# Reader.net
KiCad netlist of a schematic drawn in EAGLE
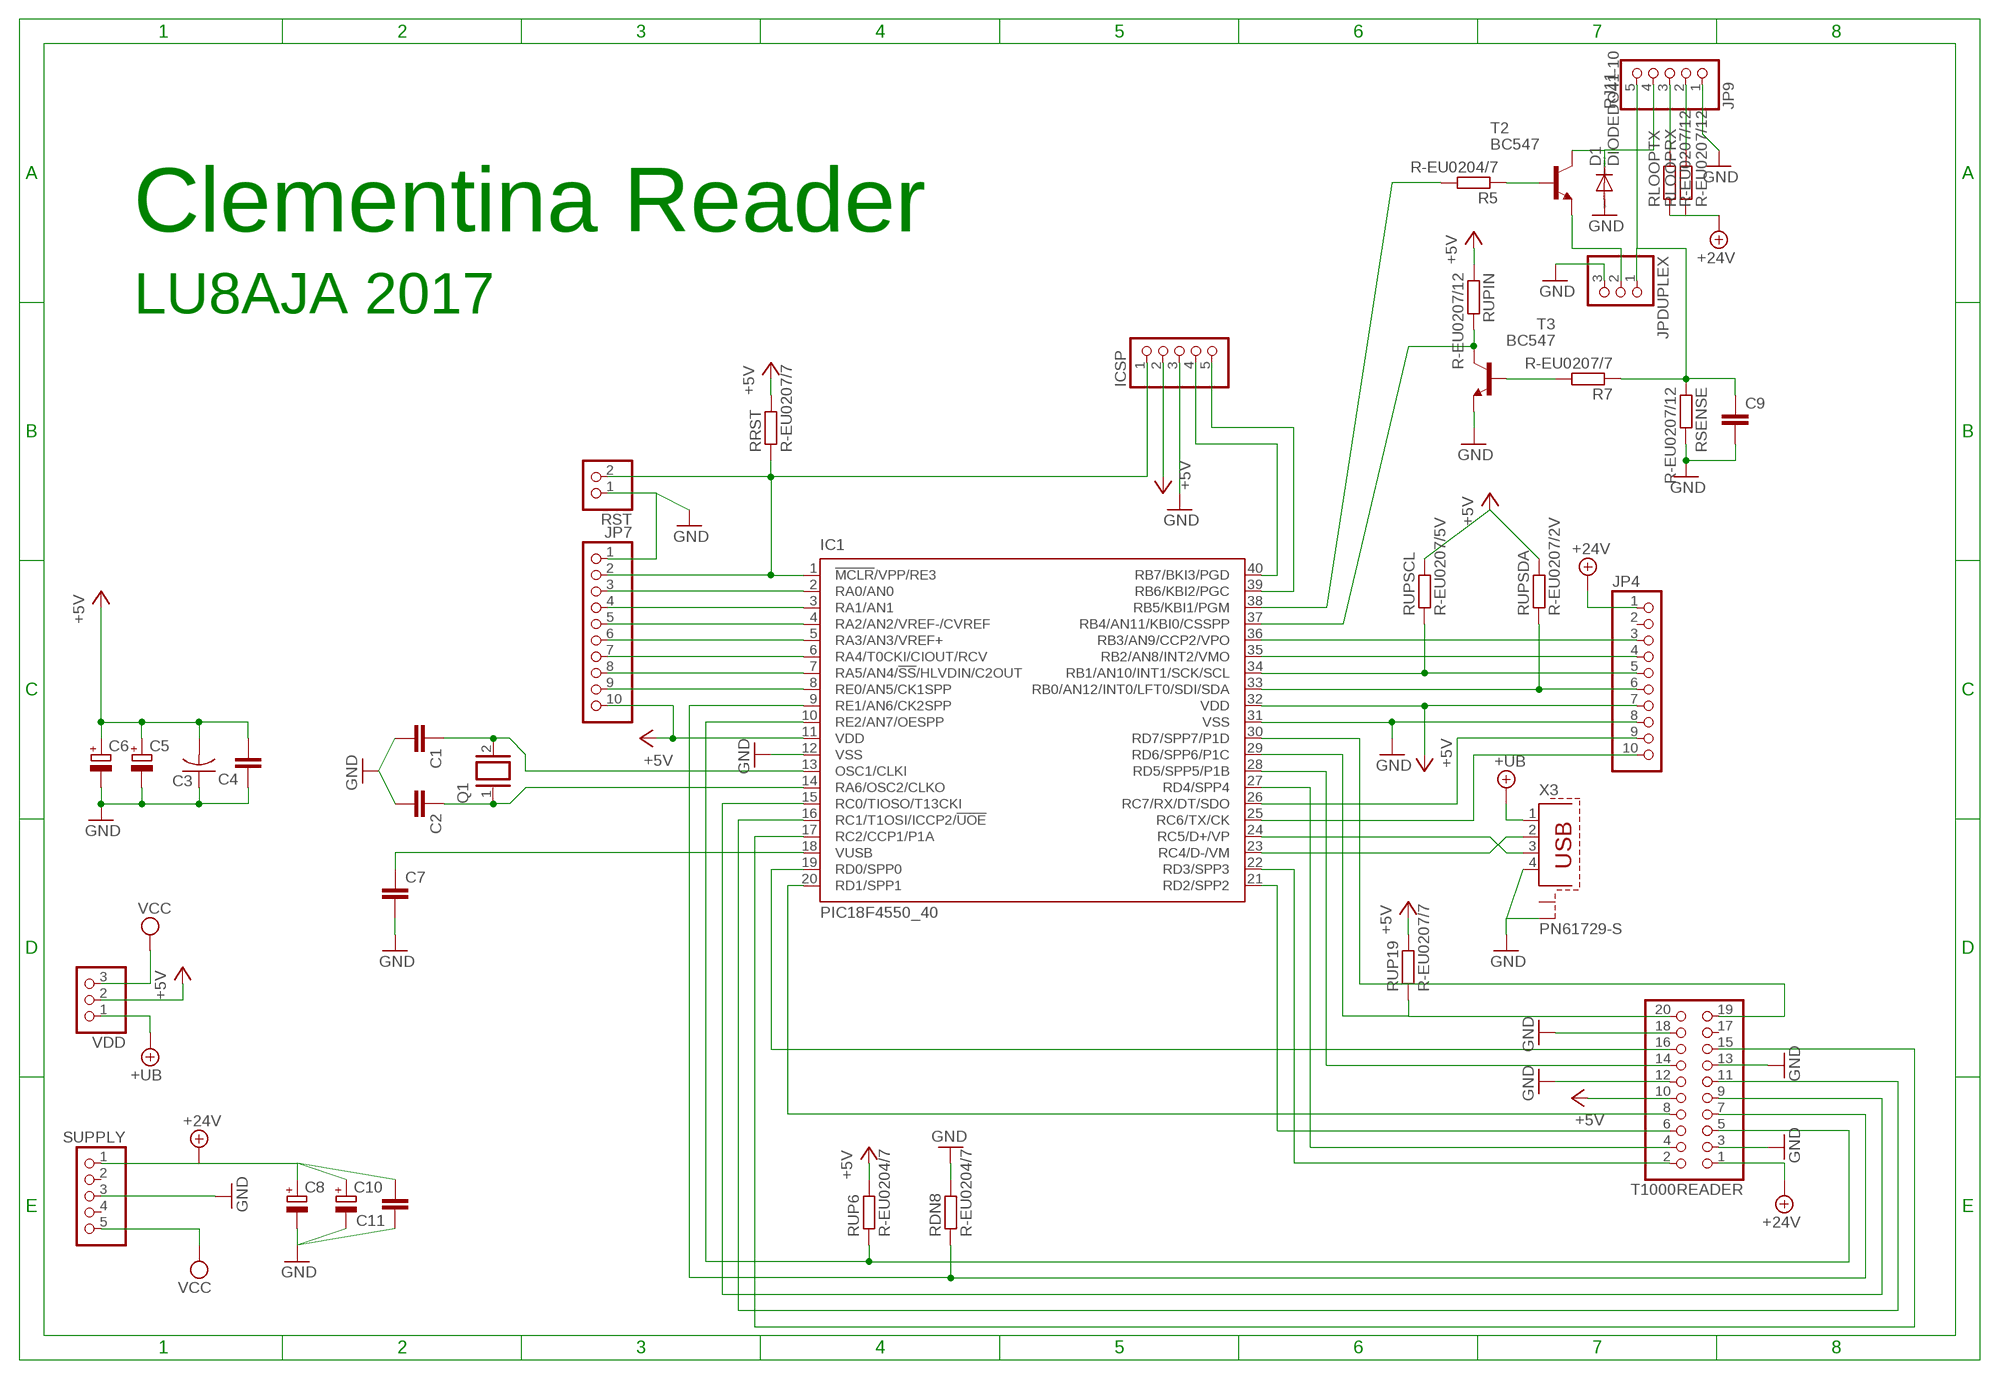
[diagram p0: schematic, sheet 1]

(export (version "E")
  (design (tool "Eeschema 10.0.6"))
  (components
    (comp (ref "C1")
      (value "C-EU025-025X050")
      (footprint "eagle-import:C025-025X050")
      (libsource (lib "eagle-import") (part "rcl_C-EU025-025X050"))
    )
    (comp (ref "C2")
      (value "C-EU025-025X050")
      (footprint "eagle-import:C025-025X050")
      (libsource (lib "eagle-import") (part "rcl_C-EU025-025X050"))
    )
    (comp (ref "C3")
      (value "C-US025-024X044")
      (footprint "eagle-import:C025-024X044")
      (libsource (lib "eagle-import") (part "C-US025-024X044"))
    )
    (comp (ref "C4")
      (value "C-EU025-030X050")
      (footprint "eagle-import:C025-030X050")
      (libsource (lib "eagle-import") (part "C-EU025-030X050"))
    )
    (comp (ref "C5")
      (value "CPOL-EUE2.5-6")
      (footprint "eagle-import:E2,5-6")
      (libsource (lib "eagle-import") (part "CPOL-EUE2.5-6"))
    )
    (comp (ref "C6")
      (value "CPOL-EUE5-8.5")
      (footprint "eagle-import:E5-8,5")
      (libsource (lib "eagle-import") (part "rcl_CPOL-EUE5-8.5"))
    )
    (comp (ref "C7")
      (value "C-EU050-025X075")
      (footprint "eagle-import:C050-025X075")
      (libsource (lib "eagle-import") (part "C-EU050-025X075"))
    )
    (comp (ref "C8")
      (value "CPOL-EUE5-8.5")
      (footprint "eagle-import:E5-8,5")
      (libsource (lib "eagle-import") (part "CPOL-EUE5-8.5"))
    )
    (comp (ref "C9")
      (value "C-EU050-024X044")
      (footprint "eagle-import:C050-024X044")
      (libsource (lib "eagle-import") (part "C-EU050-024X044"))
    )
    (comp (ref "C10")
      (value "CPOL-EUE5-8.5")
      (footprint "eagle-import:E5-8,5")
      (libsource (lib "eagle-import") (part "CPOL-EUE5-8.5"))
    )
    (comp (ref "C11")
      (value "C-EU025-030X050")
      (footprint "eagle-import:C025-030X050")
      (libsource (lib "eagle-import") (part "C-EU025-030X050"))
    )
    (comp (ref "D1")
      (value "DIODEDO41-10")
      (footprint "eagle-import:DO41-10")
      (libsource (lib "eagle-import") (part "DIODEDO41-10"))
    )
    (comp (ref "IC1")
      (value "PIC18F4550_40")
      (footprint "eagle-import:DIL40")
      (fields (field (name "MF") "MICROCHIP") (field (name "MPN") "PIC18F4550-I/P"))
      (libsource (lib "eagle-import") (part "PIC18F4_40550"))
    )
    (comp (ref "ICSP")
      (value "PINHD-1X5")
      (footprint "eagle-import:1X05")
      (libsource (lib "eagle-import") (part "PINHD-1X5"))
    )
    (comp (ref "JP4")
      (value "PINHD-1X10")
      (footprint "eagle-import:1X10")
      (libsource (lib "eagle-import") (part "PINHD-1X10"))
    )
    (comp (ref "JP7")
      (value "PINHD-1X10")
      (footprint "eagle-import:1X10")
      (libsource (lib "eagle-import") (part "PINHD-1X10"))
    )
    (comp (ref "JP9")
      (value "RJ11")
      (footprint "eagle-import:1X05")
      (libsource (lib "eagle-import") (part "PINHD-1X5"))
    )
    (comp (ref "JPDUPLEX")
      (value "PINHD-1X3")
      (footprint "eagle-import:1X03")
      (libsource (lib "eagle-import") (part "PINHD-1X3"))
    )
    (comp (ref "Q1")
      (value "XTAL/S")
      (footprint "eagle-import:QS")
      (libsource (lib "eagle-import") (part "XTAL/S"))
    )
    (comp (ref "R5")
      (value "R-EU0204/7")
      (footprint "eagle-import:0204_7")
      (libsource (lib "eagle-import") (part "R-EU0204/7"))
    )
    (comp (ref "R7")
      (value "R-EU0207/7")
      (footprint "eagle-import:0207_7")
      (libsource (lib "eagle-import") (part "R-EU0207/7"))
    )
    (comp (ref "RDN8")
      (value "R-EU0204/7")
      (footprint "eagle-import:0204_7")
      (libsource (lib "eagle-import") (part "R-EU0204/7"))
    )
    (comp (ref "RLOOPRX")
      (value "R-EU0207/12")
      (footprint "eagle-import:0207_12")
      (libsource (lib "eagle-import") (part "R-EU0207/12"))
    )
    (comp (ref "RLOOPTX")
      (value "R-EU0207/12")
      (footprint "eagle-import:0207_12")
      (libsource (lib "eagle-import") (part "R-EU0207/12"))
    )
    (comp (ref "RRST")
      (value "R-EU0207/7")
      (footprint "eagle-import:0207_7")
      (libsource (lib "eagle-import") (part "R-EU0207/7"))
    )
    (comp (ref "RSENSE")
      (value "R-EU0207/12")
      (footprint "eagle-import:0207_12")
      (libsource (lib "eagle-import") (part "R-EU0207/12"))
    )
    (comp (ref "RST")
      (value "PINHD-1X2")
      (footprint "eagle-import:1X02")
      (libsource (lib "eagle-import") (part "PINHD-1X2"))
    )
    (comp (ref "RUP6")
      (value "R-EU0204/7")
      (footprint "eagle-import:0204_7")
      (libsource (lib "eagle-import") (part "R-EU0204/7"))
    )
    (comp (ref "RUP19")
      (value "R-EU0207/7")
      (footprint "eagle-import:0207_7")
      (libsource (lib "eagle-import") (part "R-EU0207/7"))
    )
    (comp (ref "RUPIN")
      (value "R-EU0207/12")
      (footprint "eagle-import:0207_12")
      (libsource (lib "eagle-import") (part "R-EU0207/12"))
    )
    (comp (ref "RUPSCL")
      (value "R-EU0207/5V")
      (footprint "eagle-import:0207_5V")
      (libsource (lib "eagle-import") (part "R-EU0207/5V"))
    )
    (comp (ref "RUPSDA")
      (value "R-EU0207/2V")
      (footprint "eagle-import:0207_2V")
      (libsource (lib "eagle-import") (part "R-EU0207/2V"))
    )
    (comp (ref "SUPPLY")
      (value "PINHD-1X5")
      (footprint "eagle-import:1X05")
      (libsource (lib "eagle-import") (part "PINHD-1X5"))
    )
    (comp (ref "T2")
      (value "BC547")
      (footprint "eagle-import:TO92")
      (libsource (lib "eagle-import") (part "BC547"))
    )
    (comp (ref "T3")
      (value "BC547")
      (footprint "eagle-import:TO92")
      (libsource (lib "eagle-import") (part "BC547"))
    )
    (comp (ref "T1000READER")
      (value "PINHD-2X10")
      (footprint "eagle-import:2X10")
      (libsource (lib "eagle-import") (part "PINHD-2X10"))
    )
    (comp (ref "VDD")
      (value "PINHD-1X3")
      (footprint "eagle-import:1X03")
      (libsource (lib "eagle-import") (part "PINHD-1X3"))
    )
    (comp (ref "X3")
      (value "PN61729-S")
      (footprint "eagle-import:PN61729-S")
      (libsource (lib "eagle-import") (part "PN61729-S"))
    )
  )
  (nets
    (net (code "1") (name "+5V") (class "Default")
      (node (ref "C3") (pin "2") (pinfunction "2_2") (pintype "passive"))
      (node (ref "C4") (pin "2") (pinfunction "2_2") (pintype "passive"))
      (node (ref "C5") (pin "+") (pinfunction "+_+") (pintype "passive"))
      (node (ref "C6") (pin "+") (pinfunction "+_+") (pintype "passive"))
      (node (ref "IC1") (pin "11") (pinfunction "VDD_11") (pintype "power_in"))
      (node (ref "IC1") (pin "32") (pinfunction "VDD_32") (pintype "power_in"))
      (node (ref "ICSP") (pin "2") (pinfunction "2_2") (pintype "passive"))
      (node (ref "JP4") (pin "7") (pinfunction "7_7") (pintype "passive"))
      (node (ref "JP7") (pin "10") (pinfunction "10_10") (pintype "passive"))
      (node (ref "RRST") (pin "2") (pinfunction "2_2") (pintype "passive"))
      (node (ref "RUP19") (pin "2") (pinfunction "2_2") (pintype "passive"))
      (node (ref "RUP6") (pin "2") (pinfunction "2_2") (pintype "passive"))
      (node (ref "RUPIN") (pin "1") (pinfunction "1_1") (pintype "passive"))
      (node (ref "RUPSCL") (pin "2") (pinfunction "2_2") (pintype "passive"))
      (node (ref "RUPSDA") (pin "2") (pinfunction "2_2") (pintype "passive"))
      (node (ref "T1000READER") (pin "10") (pinfunction "10_10") (pintype "passive"))
      (node (ref "VDD") (pin "2") (pinfunction "2_2") (pintype "passive"))
    )
    (net (code "2") (name "+24V") (class "Default")
      (node (ref "C10") (pin "+") (pinfunction "+_+") (pintype "passive"))
      (node (ref "C11") (pin "2") (pinfunction "2_2") (pintype "passive"))
      (node (ref "C8") (pin "+") (pinfunction "+_+") (pintype "passive"))
      (node (ref "JP4") (pin "1") (pinfunction "1_1") (pintype "passive"))
      (node (ref "RLOOPRX") (pin "1") (pinfunction "1_1") (pintype "passive"))
      (node (ref "RLOOPTX") (pin "1") (pinfunction "1_1") (pintype "passive"))
      (node (ref "SUPPLY") (pin "1") (pinfunction "1_1") (pintype "passive"))
      (node (ref "T1000READER") (pin "1") (pinfunction "1_1") (pintype "passive"))
    )
    (net (code "3") (name "+UB") (class "Default")
      (node (ref "VDD") (pin "1") (pinfunction "1_1") (pintype "passive"))
      (node (ref "X3") (pin "1") (pinfunction "1_1") (pintype "passive"))
    )
    (net (code "4") (name "GND") (class "Default")
      (node (ref "C1") (pin "2") (pinfunction "2_2") (pintype "passive"))
      (node (ref "C10") (pin "-") (pinfunction "-_-") (pintype "passive"))
      (node (ref "C11") (pin "1") (pinfunction "1_1") (pintype "passive"))
      (node (ref "C2") (pin "2") (pinfunction "2_2") (pintype "passive"))
      (node (ref "C3") (pin "1") (pinfunction "1_1") (pintype "passive"))
      (node (ref "C4") (pin "1") (pinfunction "1_1") (pintype "passive"))
      (node (ref "C5") (pin "-") (pinfunction "-_-") (pintype "passive"))
      (node (ref "C6") (pin "-") (pinfunction "-_-") (pintype "passive"))
      (node (ref "C7") (pin "2") (pinfunction "2_2") (pintype "passive"))
      (node (ref "C8") (pin "-") (pinfunction "-_-") (pintype "passive"))
      (node (ref "C9") (pin "2") (pinfunction "2_2") (pintype "passive"))
      (node (ref "D1") (pin "A") (pinfunction "A_A") (pintype "passive"))
      (node (ref "IC1") (pin "12") (pinfunction "VSS_12") (pintype "power_in"))
      (node (ref "IC1") (pin "31") (pinfunction "VSS_31") (pintype "power_in"))
      (node (ref "ICSP") (pin "3") (pinfunction "3_3") (pintype "passive"))
      (node (ref "JP4") (pin "8") (pinfunction "8_8") (pintype "passive"))
      (node (ref "JP7") (pin "1") (pinfunction "1_1") (pintype "passive"))
      (node (ref "JP9") (pin "1") (pinfunction "1_1") (pintype "passive"))
      (node (ref "JPDUPLEX") (pin "3") (pinfunction "3_3") (pintype "passive"))
      (node (ref "RDN8") (pin "2") (pinfunction "2_2") (pintype "passive"))
      (node (ref "RSENSE") (pin "2") (pinfunction "2_2") (pintype "passive"))
      (node (ref "RST") (pin "1") (pinfunction "1_1") (pintype "passive"))
      (node (ref "SUPPLY") (pin "3") (pinfunction "3_3") (pintype "passive"))
      (node (ref "T1000READER") (pin "12") (pinfunction "12_12") (pintype "passive"))
      (node (ref "T1000READER") (pin "13") (pinfunction "13_13") (pintype "passive"))
      (node (ref "T1000READER") (pin "18") (pinfunction "18_18") (pintype "passive"))
      (node (ref "T1000READER") (pin "3") (pinfunction "3_3") (pintype "passive"))
      (node (ref "T3") (pin "1") (pinfunction "E_1") (pintype "passive"))
      (node (ref "X3") (pin "4") (pinfunction "4_4") (pintype "passive"))
      (node (ref "X3") (pin "S2") (pinfunction "S2_S2") (pintype "passive"))
    )
    (net (code "5") (name "Net-(C9-Pad1)") (class "Default")
      (node (ref "C9") (pin "1") (pinfunction "1_1") (pintype "passive"))
      (node (ref "JP9") (pin "5") (pinfunction "5_5") (pintype "passive"))
      (node (ref "JPDUPLEX") (pin "1") (pinfunction "1_1") (pintype "passive"))
      (node (ref "R7") (pin "1") (pinfunction "1_1") (pintype "passive"))
      (node (ref "RSENSE") (pin "1") (pinfunction "1_1") (pintype "passive"))
    )
    (net (code "6") (name "Net-(IC1-OSC1{slash}CLKI)") (class "Default")
      (node (ref "C1") (pin "1") (pinfunction "1_1") (pintype "passive"))
      (node (ref "IC1") (pin "13") (pinfunction "OSC1/CLKI_13") (pintype "input"))
      (node (ref "Q1") (pin "2") (pinfunction "2_2") (pintype "passive"))
    )
    (net (code "7") (name "Net-(IC1-RA0{slash}AN0)") (class "Default")
      (node (ref "IC1") (pin "2") (pinfunction "RA0/AN0_2") (pintype "bidirectional"))
      (node (ref "JP7") (pin "3") (pinfunction "3_3") (pintype "passive"))
    )
    (net (code "8") (name "Net-(IC1-RA1{slash}AN1)") (class "Default")
      (node (ref "IC1") (pin "3") (pinfunction "RA1/AN1_3") (pintype "bidirectional"))
      (node (ref "JP7") (pin "4") (pinfunction "4_4") (pintype "passive"))
    )
    (net (code "9") (name "Net-(IC1-RA2{slash}AN2{slash}VREF-{slash}CVREF)") (class "Default")
      (node (ref "IC1") (pin "4") (pinfunction "RA2/AN2/VREF-/CVREF_4") (pintype "bidirectional"))
      (node (ref "JP7") (pin "5") (pinfunction "5_5") (pintype "passive"))
    )
    (net (code "10") (name "Net-(IC1-RA3{slash}AN3{slash}VREF+)") (class "Default")
      (node (ref "IC1") (pin "5") (pinfunction "RA3/AN3/VREF+_5") (pintype "bidirectional"))
      (node (ref "JP7") (pin "6") (pinfunction "6_6") (pintype "passive"))
    )
    (net (code "11") (name "Net-(IC1-RA4{slash}T0CKI{slash}CIOUT{slash}RCV)") (class "Default")
      (node (ref "IC1") (pin "6") (pinfunction "RA4/T0CKI/CIOUT/RCV_6") (pintype "bidirectional"))
      (node (ref "JP7") (pin "7") (pinfunction "7_7") (pintype "passive"))
    )
    (net (code "12") (name "Net-(IC1-RA5{slash}AN4{slash}~{SS}{slash}HLVDIN{slash}C2OUT)") (class "Default")
      (node (ref "IC1") (pin "7") (pinfunction "RA5/AN4/~{SS}/HLVDIN/C2OUT_7") (pintype "bidirectional"))
      (node (ref "JP7") (pin "8") (pinfunction "8_8") (pintype "passive"))
    )
    (net (code "13") (name "Net-(IC1-RA6{slash}OSC2{slash}CLKO)") (class "Default")
      (node (ref "C2") (pin "1") (pinfunction "1_1") (pintype "passive"))
      (node (ref "IC1") (pin "14") (pinfunction "RA6/OSC2/CLKO_14") (pintype "output"))
      (node (ref "Q1") (pin "1") (pinfunction "1_1") (pintype "passive"))
    )
    (net (code "14") (name "Net-(IC1-RB0{slash}AN12{slash}INT0{slash}LFT0{slash}SDI{slash}SDA)") (class "Default")
      (node (ref "IC1") (pin "33") (pinfunction "RB0/AN12/INT0/LFT0/SDI/SDA_33") (pintype "bidirectional"))
      (node (ref "JP4") (pin "6") (pinfunction "6_6") (pintype "passive"))
      (node (ref "RUPSDA") (pin "1") (pinfunction "1_1") (pintype "passive"))
    )
    (net (code "15") (name "Net-(IC1-RB1{slash}AN10{slash}INT1{slash}SCK{slash}SCL)") (class "Default")
      (node (ref "IC1") (pin "34") (pinfunction "RB1/AN10/INT1/SCK/SCL_34") (pintype "bidirectional"))
      (node (ref "JP4") (pin "5") (pinfunction "5_5") (pintype "passive"))
      (node (ref "RUPSCL") (pin "1") (pinfunction "1_1") (pintype "passive"))
    )
    (net (code "16") (name "Net-(IC1-RB2{slash}AN8{slash}INT2{slash}VMO)") (class "Default")
      (node (ref "IC1") (pin "35") (pinfunction "RB2/AN8/INT2/VMO_35") (pintype "bidirectional"))
      (node (ref "JP4") (pin "4") (pinfunction "4_4") (pintype "passive"))
    )
    (net (code "17") (name "Net-(IC1-RB3{slash}AN9{slash}CCP2{slash}VPO)") (class "Default")
      (node (ref "IC1") (pin "36") (pinfunction "RB3/AN9/CCP2/VPO_36") (pintype "bidirectional"))
      (node (ref "JP4") (pin "3") (pinfunction "3_3") (pintype "passive"))
    )
    (net (code "18") (name "Net-(IC1-RB4{slash}AN11{slash}KBI0{slash}CSSPP)") (class "Default")
      (node (ref "IC1") (pin "37") (pinfunction "RB4/AN11/KBI0/CSSPP_37") (pintype "bidirectional"))
      (node (ref "RUPIN") (pin "2") (pinfunction "2_2") (pintype "passive"))
      (node (ref "T3") (pin "3") (pinfunction "C_3") (pintype "passive"))
    )
    (net (code "19") (name "Net-(IC1-RB5{slash}KBI1{slash}PGM)") (class "Default")
      (node (ref "IC1") (pin "38") (pinfunction "RB5/KBI1/PGM_38") (pintype "bidirectional"))
      (node (ref "R5") (pin "2") (pinfunction "2_2") (pintype "passive"))
    )
    (net (code "20") (name "Net-(IC1-RB6{slash}KBI2{slash}PGC)") (class "Default")
      (node (ref "IC1") (pin "39") (pinfunction "RB6/KBI2/PGC_39") (pintype "bidirectional"))
      (node (ref "ICSP") (pin "5") (pinfunction "5_5") (pintype "passive"))
    )
    (net (code "21") (name "Net-(IC1-RB7{slash}BKI3{slash}PGD)") (class "Default")
      (node (ref "IC1") (pin "40") (pinfunction "RB7/BKI3/PGD_40") (pintype "bidirectional"))
      (node (ref "ICSP") (pin "4") (pinfunction "4_4") (pintype "passive"))
    )
    (net (code "22") (name "Net-(IC1-RC0{slash}TIOSO{slash}T13CKI)") (class "Default")
      (node (ref "IC1") (pin "15") (pinfunction "RC0/TIOSO/T13CKI_15") (pintype "bidirectional"))
      (node (ref "T1000READER") (pin "9") (pinfunction "9_9") (pintype "passive"))
    )
    (net (code "23") (name "Net-(IC1-RC1{slash}T1OSI{slash}ICCP2{slash}~{UOE})") (class "Default")
      (node (ref "IC1") (pin "16") (pinfunction "RC1/T1OSI/ICCP2/~{UOE}_16") (pintype "bidirectional"))
      (node (ref "T1000READER") (pin "11") (pinfunction "11_11") (pintype "passive"))
    )
    (net (code "24") (name "Net-(IC1-RC2{slash}CCP1{slash}P1A)") (class "Default")
      (node (ref "IC1") (pin "17") (pinfunction "RC2/CCP1/P1A_17") (pintype "bidirectional"))
      (node (ref "T1000READER") (pin "15") (pinfunction "15_15") (pintype "passive"))
    )
    (net (code "25") (name "Net-(IC1-RC4{slash}D-{slash}VM)") (class "Default")
      (node (ref "IC1") (pin "23") (pinfunction "RC4/D-/VM_23") (pintype "bidirectional"))
      (node (ref "X3") (pin "2") (pinfunction "2_2") (pintype "passive"))
    )
    (net (code "26") (name "Net-(IC1-RC5{slash}D+{slash}VP)") (class "Default")
      (node (ref "IC1") (pin "24") (pinfunction "RC5/D+/VP_24") (pintype "bidirectional"))
      (node (ref "X3") (pin "3") (pinfunction "3_3") (pintype "passive"))
    )
    (net (code "27") (name "Net-(IC1-RC6{slash}TX{slash}CK)") (class "Default")
      (node (ref "IC1") (pin "25") (pinfunction "RC6/TX/CK_25") (pintype "bidirectional"))
      (node (ref "JP4") (pin "10") (pinfunction "10_10") (pintype "passive"))
    )
    (net (code "28") (name "Net-(IC1-RC7{slash}RX{slash}DT{slash}SDO)") (class "Default")
      (node (ref "IC1") (pin "26") (pinfunction "RC7/RX/DT/SDO_26") (pintype "bidirectional"))
      (node (ref "JP4") (pin "9") (pinfunction "9_9") (pintype "passive"))
    )
    (net (code "29") (name "Net-(IC1-RD0{slash}SPP0)") (class "Default")
      (node (ref "IC1") (pin "19") (pinfunction "RD0/SPP0_19") (pintype "bidirectional"))
      (node (ref "T1000READER") (pin "16") (pinfunction "16_16") (pintype "passive"))
    )
    (net (code "30") (name "Net-(IC1-RD1{slash}SPP1)") (class "Default")
      (node (ref "IC1") (pin "20") (pinfunction "RD1/SPP1_20") (pintype "bidirectional"))
      (node (ref "T1000READER") (pin "8") (pinfunction "8_8") (pintype "passive"))
    )
    (net (code "31") (name "Net-(IC1-RD2{slash}SPP2)") (class "Default")
      (node (ref "IC1") (pin "21") (pinfunction "RD2/SPP2_21") (pintype "bidirectional"))
      (node (ref "T1000READER") (pin "6") (pinfunction "6_6") (pintype "passive"))
    )
    (net (code "32") (name "Net-(IC1-RD3{slash}SPP3)") (class "Default")
      (node (ref "IC1") (pin "22") (pinfunction "RD3/SPP3_22") (pintype "bidirectional"))
      (node (ref "T1000READER") (pin "2") (pinfunction "2_2") (pintype "passive"))
    )
    (net (code "33") (name "Net-(IC1-RD4{slash}SPP4)") (class "Default")
      (node (ref "IC1") (pin "27") (pinfunction "RD4/SPP4_27") (pintype "bidirectional"))
      (node (ref "T1000READER") (pin "4") (pinfunction "4_4") (pintype "passive"))
    )
    (net (code "34") (name "Net-(IC1-RD5{slash}SPP5{slash}P1B)") (class "Default")
      (node (ref "IC1") (pin "28") (pinfunction "RD5/SPP5/P1B_28") (pintype "bidirectional"))
      (node (ref "T1000READER") (pin "14") (pinfunction "14_14") (pintype "passive"))
    )
    (net (code "35") (name "Net-(IC1-RD6{slash}SPP6{slash}P1C)") (class "Default")
      (node (ref "IC1") (pin "29") (pinfunction "RD6/SPP6/P1C_29") (pintype "bidirectional"))
      (node (ref "RUP19") (pin "1") (pinfunction "1_1") (pintype "passive"))
      (node (ref "T1000READER") (pin "20") (pinfunction "20_20") (pintype "passive"))
    )
    (net (code "36") (name "Net-(IC1-RD7{slash}SPP7{slash}P1D)") (class "Default")
      (node (ref "IC1") (pin "30") (pinfunction "RD7/SPP7/P1D_30") (pintype "bidirectional"))
      (node (ref "T1000READER") (pin "19") (pinfunction "19_19") (pintype "passive"))
    )
    (net (code "37") (name "Net-(IC1-RE0{slash}AN5{slash}CK1SPP)") (class "Default")
      (node (ref "IC1") (pin "8") (pinfunction "RE0/AN5/CK1SPP_8") (pintype "bidirectional"))
      (node (ref "JP7") (pin "9") (pinfunction "9_9") (pintype "passive"))
    )
    (net (code "38") (name "Net-(IC1-RE1{slash}AN6{slash}CK2SPP)") (class "Default")
      (node (ref "IC1") (pin "9") (pinfunction "RE1/AN6/CK2SPP_9") (pintype "bidirectional"))
      (node (ref "RDN8") (pin "1") (pinfunction "1_1") (pintype "passive"))
      (node (ref "T1000READER") (pin "7") (pinfunction "7_7") (pintype "passive"))
    )
    (net (code "39") (name "Net-(IC1-RE2{slash}AN7{slash}OESPP)") (class "Default")
      (node (ref "IC1") (pin "10") (pinfunction "RE2/AN7/OESPP_10") (pintype "bidirectional"))
      (node (ref "RUP6") (pin "1") (pinfunction "1_1") (pintype "passive"))
      (node (ref "T1000READER") (pin "5") (pinfunction "5_5") (pintype "passive"))
    )
    (net (code "40") (name "Net-(IC1-VUSB)") (class "Default")
      (node (ref "C7") (pin "1") (pinfunction "1_1") (pintype "passive"))
      (node (ref "IC1") (pin "18") (pinfunction "VUSB_18") (pintype "bidirectional"))
    )
    (net (code "41") (name "Net-(IC1-~{MCLR}{slash}VPP{slash}RE3)") (class "Default")
      (node (ref "IC1") (pin "1") (pinfunction "~{MCLR}/VPP/RE3_1") (pintype "input"))
      (node (ref "ICSP") (pin "1") (pinfunction "1_1") (pintype "passive"))
      (node (ref "JP7") (pin "2") (pinfunction "2_2") (pintype "passive"))
      (node (ref "RRST") (pin "1") (pinfunction "1_1") (pintype "passive"))
      (node (ref "RST") (pin "2") (pinfunction "2_2") (pintype "passive"))
    )
    (net (code "42") (name "Net-(JP9-Pad2)") (class "Default")
      (node (ref "JP9") (pin "2") (pinfunction "2_2") (pintype "passive"))
      (node (ref "RLOOPRX") (pin "2") (pinfunction "2_2") (pintype "passive"))
    )
    (net (code "43") (name "Net-(JP9-Pad3)") (class "Default")
      (node (ref "JP9") (pin "3") (pinfunction "3_3") (pintype "passive"))
      (node (ref "RLOOPTX") (pin "2") (pinfunction "2_2") (pintype "passive"))
    )
    (net (code "44") (name "Net-(T2-B)") (class "Default")
      (node (ref "R5") (pin "1") (pinfunction "1_1") (pintype "passive"))
      (node (ref "T2") (pin "2") (pinfunction "B_2") (pintype "passive"))
    )
    (net (code "45") (name "Net-(T2-C)") (class "Default")
      (node (ref "D1") (pin "C") (pinfunction "C_C") (pintype "passive"))
      (node (ref "JP9") (pin "4") (pinfunction "4_4") (pintype "passive"))
      (node (ref "T2") (pin "3") (pinfunction "C_3") (pintype "passive"))
    )
    (net (code "46") (name "Net-(T2-E)") (class "Default")
      (node (ref "JPDUPLEX") (pin "2") (pinfunction "2_2") (pintype "passive"))
      (node (ref "T2") (pin "1") (pinfunction "E_1") (pintype "passive"))
    )
    (net (code "47") (name "Net-(T3-B)") (class "Default")
      (node (ref "R7") (pin "2") (pinfunction "2_2") (pintype "passive"))
      (node (ref "T3") (pin "2") (pinfunction "B_2") (pintype "passive"))
    )
    (net (code "48") (name "VCC") (class "Default")
      (node (ref "SUPPLY") (pin "5") (pinfunction "5_5") (pintype "passive"))
      (node (ref "VDD") (pin "3") (pinfunction "3_3") (pintype "passive"))
    )
    (net (code "49") (name "unconnected-(JP4-Pad2)") (class "Default")
      (node (ref "JP4") (pin "2") (pinfunction "2_2") (pintype "passive"))
    )
    (net (code "50") (name "unconnected-(SUPPLY-Pad2)") (class "Default")
      (node (ref "SUPPLY") (pin "2") (pinfunction "2_2") (pintype "passive"))
    )
    (net (code "51") (name "unconnected-(SUPPLY-Pad4)") (class "Default")
      (node (ref "SUPPLY") (pin "4") (pinfunction "4_4") (pintype "passive"))
    )
    (net (code "52") (name "unconnected-(T1000READER-Pad17)") (class "Default")
      (node (ref "T1000READER") (pin "17") (pinfunction "17_17") (pintype "passive"))
    )
    (net (code "53") (name "unconnected-(X3-PadS1)") (class "Default")
      (node (ref "X3") (pin "S1") (pinfunction "S1_S1") (pintype "passive"))
    )
  )
)
